# Driver_Morpheus_PONTE_H.net
KiCad netlist of a schematic drawn in Altium Designer
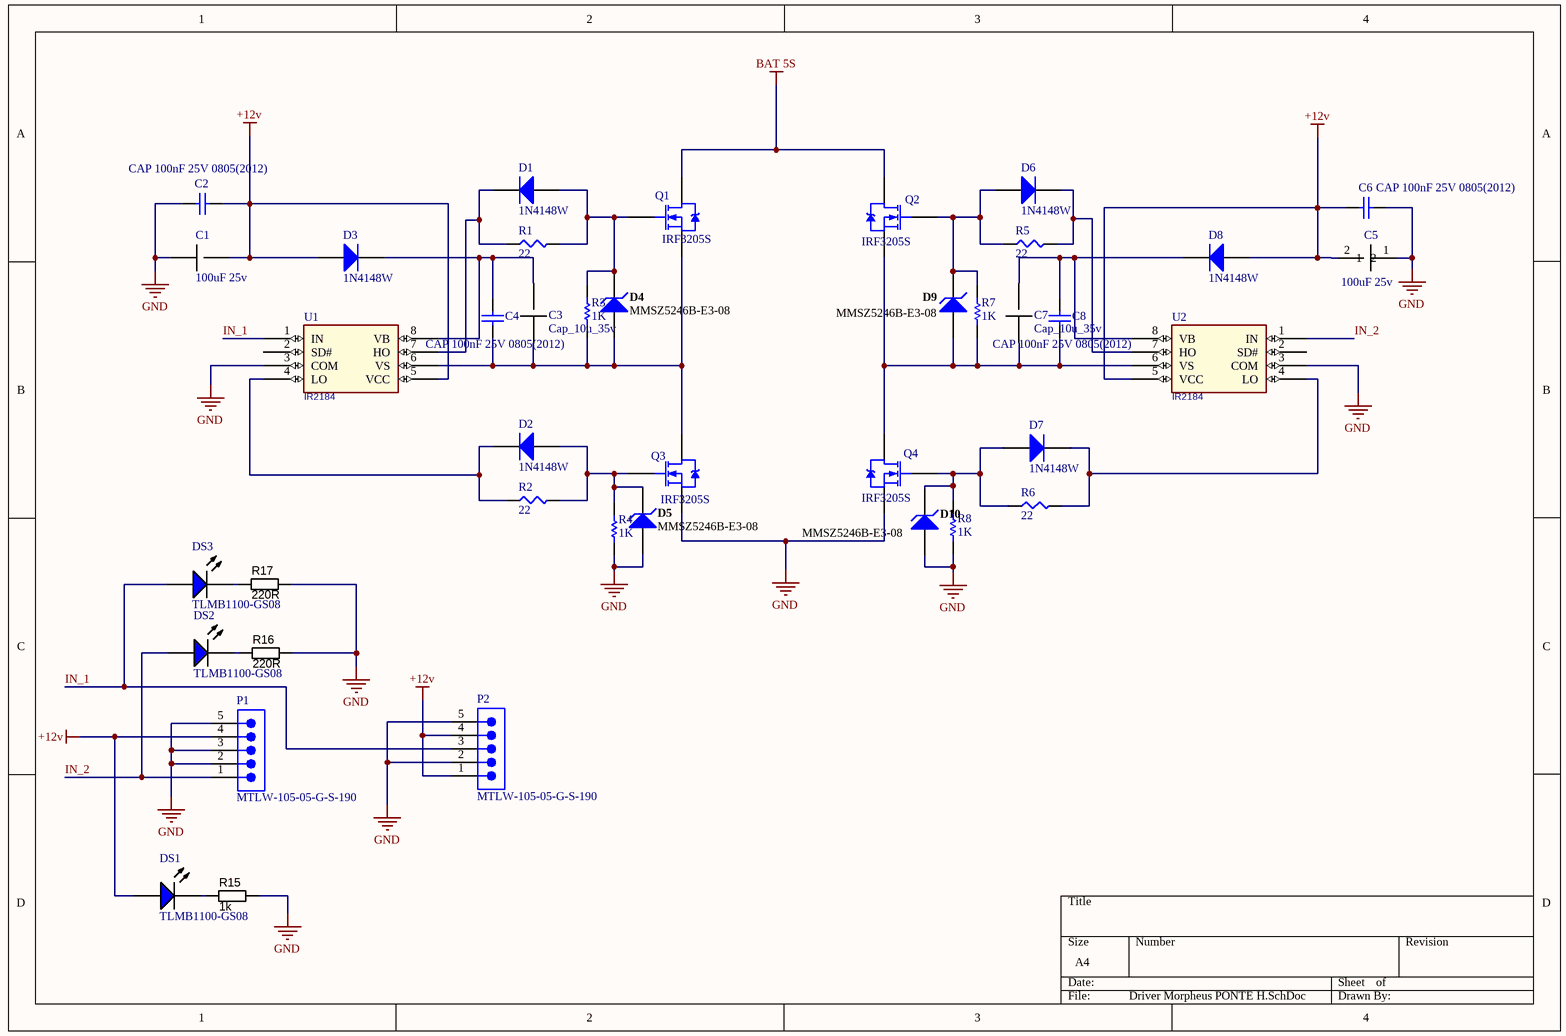
[diagram p0: Driver Morpheus PONTE H.SchDoc]

(export (version "E")
  (design (tool "Eeschema 10.0.6"))
  (components
    (comp (ref "C1")
      (value "100uF 25v")
      (footprint "CAPAE9083X70M")
      (libsource (lib "LibSanhaço2017") (part "Cap_10u_35v"))
    )
    (comp (ref "C2")
      (value "CAP 100nF 25V 0805(2012)")
      (footprint "CAPC0805(2012)145_M")
      (description "CAP 100nF 25V ±5% 0805 (2012 Metric) Thickness 1.45mm SMD")
      (fields (field (name "TOLERANCE") "Â±5%"))
      (libsource (lib "Altium Content Vault") (part "CAP"))
    )
    (comp (ref "C3")
      (value "Cap_10u_35v")
      (footprint "CAP POL 2917/7343")
      (libsource (lib "LibSanhaço2017") (part "Cap_10u_35v"))
    )
    (comp (ref "C4")
      (value "CAP 100nF 25V 0805(2012)")
      (footprint "CAPC0805(2012)145_M")
      (description "CAP 100nF 25V ±5% 0805 (2012 Metric) Thickness 1.45mm SMD")
      (fields (field (name "TOLERANCE") "Â±5%"))
      (libsource (lib "Altium Content Vault") (part "CAP"))
    )
    (comp (ref "C5")
      (value "100uF 25v")
      (footprint "CAPAE9083X70M")
      (description "Cap Tântalo")
      (libsource (lib "LibSanhaço2017") (part "Cap_100u_25v"))
    )
    (comp (ref "C6")
      (value "CAP 100nF 25V 0805(2012)")
      (footprint "CAPC0805(2012)145_M")
      (description "CAP 100nF 25V ±5% 0805 (2012 Metric) Thickness 1.45mm SMD")
      (fields (field (name "TOLERANCE") "Â±5%"))
      (libsource (lib "Altium Content Vault") (part "CAP"))
    )
    (comp (ref "C7")
      (value "Cap_10u_35v")
      (footprint "CAP POL 2917/7343")
      (libsource (lib "LibSanhaço2017") (part "Cap_10u_35v"))
    )
    (comp (ref "C8")
      (value "CAP 100nF 25V 0805(2012)")
      (footprint "CAPC0805(2012)145_M")
      (description "CAP 100nF 25V ±5% 0805 (2012 Metric) Thickness 1.45mm SMD")
      (fields (field (name "TOLERANCE") "Â±5%"))
      (libsource (lib "Altium Content Vault") (part "CAP"))
    )
    (comp (ref "D1")
      (value "1N4148W")
      (footprint "JSCJ-SOD-123-2_V")
      (description "Fast Switching Diode, 75 V, 150 mA, 2-Pin 2.7 x 1.6 x 1.25 mm SMD, Tape and Reel")
      (fields (field (name "MANUFACTURER") "Changjiang Electronics"))
      (libsource (lib "Altium Content Vault") (part "CMP-0914-00001-1"))
    )
    (comp (ref "D2")
      (value "1N4148W")
      (footprint "JSCJ-SOD-123-2_V")
      (description "Fast Switching Diode, 75 V, 150 mA, 2-Pin 2.7 x 1.6 x 1.25 mm SMD, Tape and Reel")
      (fields (field (name "MANUFACTURER") "Changjiang Electronics"))
      (libsource (lib "Altium Content Vault") (part "CMP-0914-00001-1"))
    )
    (comp (ref "D3")
      (value "1N4148W")
      (footprint "JSCJ-SOD-123-2_V")
      (description "Fast Switching Diode, 75 V, 150 mA, 2-Pin 2.7 x 1.6 x 1.25 mm SMD, Tape and Reel")
      (fields (field (name "MANUFACTURER") "Changjiang Electronics"))
      (libsource (lib "Altium Content Vault") (part "CMP-0914-00001-1"))
    )
    (comp (ref "D4")
      (value "MMSZ5246B-E3-08")
      (footprint "VISH-SOD-123-2_V")
      (description "Small Signal Zener Diode, 16 V +/- 5%, -55 to 155 degC, 2-Pin SOD-123, RoHS, Tape and Reel")
      (fields (field (name "MANUFACTURER") "Vishay Semiconductor") (field (name "TOLERANCE") "+/- 5%"))
      (libsource (lib "Altium Content Vault") (part "VISH-DZEN_A1K2-2"))
    )
    (comp (ref "D5")
      (value "MMSZ5246B-E3-08")
      (footprint "VISH-SOD-123-2_V")
      (description "Small Signal Zener Diode, 16 V +/- 5%, -55 to 155 degC, 2-Pin SOD-123, RoHS, Tape and Reel")
      (fields (field (name "MANUFACTURER") "Vishay Semiconductor") (field (name "TOLERANCE") "+/- 5%"))
      (libsource (lib "Altium Content Vault") (part "VISH-DZEN_A1K2-2"))
    )
    (comp (ref "D6")
      (value "1N4148W")
      (footprint "JSCJ-SOD-123-2_V")
      (description "Fast Switching Diode, 75 V, 150 mA, 2-Pin 2.7 x 1.6 x 1.25 mm SMD, Tape and Reel")
      (fields (field (name "MANUFACTURER") "Changjiang Electronics"))
      (libsource (lib "Altium Content Vault") (part "CMP-0914-00001-1"))
    )
    (comp (ref "D7")
      (value "1N4148W")
      (footprint "JSCJ-SOD-123-2_V")
      (description "Fast Switching Diode, 75 V, 150 mA, 2-Pin 2.7 x 1.6 x 1.25 mm SMD, Tape and Reel")
      (fields (field (name "MANUFACTURER") "Changjiang Electronics"))
      (libsource (lib "Altium Content Vault") (part "CMP-0914-00001-1"))
    )
    (comp (ref "D8")
      (value "1N4148W")
      (footprint "JSCJ-SOD-123-2_V")
      (description "Fast Switching Diode, 75 V, 150 mA, 2-Pin 2.7 x 1.6 x 1.25 mm SMD, Tape and Reel")
      (fields (field (name "MANUFACTURER") "Changjiang Electronics"))
      (libsource (lib "Altium Content Vault") (part "CMP-0914-00001-1"))
    )
    (comp (ref "D9")
      (value "MMSZ5246B-E3-08")
      (footprint "VISH-SOD-123-2_V")
      (description "Small Signal Zener Diode, 16 V +/- 5%, -55 to 155 degC, 2-Pin SOD-123, RoHS, Tape and Reel")
      (fields (field (name "MANUFACTURER") "Vishay Semiconductor") (field (name "TOLERANCE") "+/- 5%"))
      (libsource (lib "Altium Content Vault") (part "CMP-0931-00032-1"))
    )
    (comp (ref "D10")
      (value "MMSZ5246B-E3-08")
      (footprint "VISH-SOD-123-2_V")
      (description "Small Signal Zener Diode, 16 V +/- 5%, -55 to 155 degC, 2-Pin SOD-123, RoHS, Tape and Reel")
      (fields (field (name "MANUFACTURER") "Vishay Semiconductor") (field (name "TOLERANCE") "+/- 5%"))
      (libsource (lib "Altium Content Vault") (part "VISH-DZEN_A1K2-2"))
    )
    (comp (ref "DS1")
      (value "TLMB1100-GS08")
      (footprint "VISH-TLMX1100-2_V")
      (description "Blue LED, 10 mA, 3.9 V, -40 to 100 degC, 2-Pin SMD (0603), RoHS, Tape and Reel")
      (fields (field (name "TOLERANCE") "10%"))
      (libsource (lib "Altium Content Vault") (part "CMP-1666-00028-1"))
    )
    (comp (ref "DS2")
      (value "TLMB1100-GS08")
      (footprint "VISH-TLMX1100-2_V")
      (description "Blue LED, 10 mA, 3.9 V, -40 to 100 degC, 2-Pin SMD (0603), RoHS, Tape and Reel")
      (fields (field (name "TOLERANCE") "10%"))
      (libsource (lib "Altium Content Vault") (part "CMP-1666-00028-1"))
    )
    (comp (ref "DS3")
      (value "TLMB1100-GS08")
      (footprint "VISH-TLMX1100-2_V")
      (description "Blue LED, 10 mA, 3.9 V, -40 to 100 degC, 2-Pin SMD (0603), RoHS, Tape and Reel")
      (fields (field (name "TOLERANCE") "10%"))
      (libsource (lib "Altium Content Vault") (part "CMP-1666-00028-1"))
    )
    (comp (ref "P1")
      (value "MTLW-105-05-G-S-190")
      (footprint "SMTC-MTLW-105-05-X-S-190")
      (fields (field (name "MANUFACTURER") "Samtec"))
      (libsource (lib "Altium Content Vault") (part "SMTC-MTLW-105-05-X-S-190"))
    )
    (comp (ref "P2")
      (value "MTLW-105-05-G-S-190")
      (footprint "SMTC-MTLW-105-05-X-S-190")
      (fields (field (name "MANUFACTURER") "Samtec"))
      (libsource (lib "Altium Content Vault") (part "SMTC-MTLW-105-05-X-S-190"))
    )
    (comp (ref "Q1")
      (value "IRF3205S")
      (footprint "D2PAK_N")
      (description "HEXFET Power MOSFET")
      (fields (field (name "PUBLISHER") "Altium Limited"))
      (libsource (lib "IR Discrete MOSFET - Power") (part "IRF3205S"))
    )
    (comp (ref "Q2")
      (value "IRF3205S")
      (footprint "D2PAK_N")
      (description "HEXFET Power MOSFET")
      (fields (field (name "PUBLISHER") "Altium Limited"))
      (libsource (lib "IR Discrete MOSFET - Power") (part "IRF3205S"))
    )
    (comp (ref "Q3")
      (value "IRF3205S")
      (footprint "D2PAK_N")
      (description "HEXFET Power MOSFET")
      (fields (field (name "PUBLISHER") "Altium Limited"))
      (libsource (lib "IR Discrete MOSFET - Power") (part "IRF3205S"))
    )
    (comp (ref "Q4")
      (value "IRF3205S")
      (footprint "D2PAK_N")
      (description "HEXFET Power MOSFET")
      (fields (field (name "PUBLISHER") "Altium Limited"))
      (libsource (lib "IR Discrete MOSFET - Power") (part "IRF3205S"))
    )
    (comp (ref "R1")
      (value "22")
      (footprint "SMD-0603-RES")
      (description "RES SMD 22 OHM 1% 1/10W 0603")
      (fields
        (field (name "PART NUMBER") "ERJ-3EKF22R0V")
        (field (name "DIGI-KEY PART NUMBER") "P22.0HCT-ND")
      )
      (libsource (lib "Panasonic_ERJ_0603") (part "ERJ-3EKF22R0V"))
    )
    (comp (ref "R2")
      (value "22")
      (footprint "SMD-0603-RES")
      (description "RES SMD 22 OHM 1% 1/10W 0603")
      (fields
        (field (name "PART NUMBER") "ERJ-3EKF22R0V")
        (field (name "DIGI-KEY PART NUMBER") "P22.0HCT-ND")
      )
      (libsource (lib "Panasonic_ERJ_0603") (part "ERJ-3EKF22R0V"))
    )
    (comp (ref "R3")
      (value "1K")
      (footprint "RES-0402")
      (description "RES SMD 1K OHM 5% 1/16W 0402")
      (fields (field (name "Comment") "RC0402JR-071KL"))
      (libsource (lib "Schlib1") (part "RES 1K 0402"))
    )
    (comp (ref "R4")
      (value "1K")
      (footprint "RES-0402")
      (description "RES SMD 1K OHM 5% 1/16W 0402")
      (fields (field (name "Comment") "RC0402JR-071KL"))
      (libsource (lib "Schlib1") (part "RES 1K 0402"))
    )
    (comp (ref "R5")
      (value "22")
      (footprint "SMD-0603-RES")
      (description "RES SMD 22 OHM 1% 1/10W 0603")
      (fields
        (field (name "PART NUMBER") "ERJ-3EKF22R0V")
        (field (name "DIGI-KEY PART NUMBER") "P22.0HCT-ND")
      )
      (libsource (lib "Panasonic_ERJ_0603") (part "ERJ-3EKF22R0V"))
    )
    (comp (ref "R6")
      (value "22")
      (footprint "SMD-0603-RES")
      (description "RES SMD 22 OHM 1% 1/10W 0603")
      (fields
        (field (name "PART NUMBER") "ERJ-3EKF22R0V")
        (field (name "DIGI-KEY PART NUMBER") "P22.0HCT-ND")
      )
      (libsource (lib "Panasonic_ERJ_0603") (part "ERJ-3EKF22R0V"))
    )
    (comp (ref "R7")
      (value "1K")
      (footprint "RES-0402")
      (description "RES SMD 1K OHM 5% 1/16W 0402")
      (fields (field (name "Comment") "RC0402JR-071KL"))
      (libsource (lib "Schlib1") (part "RES 1K 0402"))
    )
    (comp (ref "R8")
      (value "1K")
      (footprint "RES-0402")
      (description "RES SMD 1K OHM 5% 1/16W 0402")
      (fields (field (name "Comment") "RC0402JR-071KL"))
      (libsource (lib "Schlib1") (part "RES 1K 0402"))
    )
    (comp (ref "R15")
      (value "1k")
      (footprint "RESC1608X55N")
      (description "Resistor SMD chip 220 Ohm 0.1W 5% 0603")
      (fields (field (name "TOLERANCE") "±5%") (field (name "Comment") "Thick Film"))
      (libsource (lib "PBL - Resistors") (part "RES_220R_0603_5%"))
    )
    (comp (ref "R16")
      (value "220R")
      (footprint "RESC1608X55N")
      (description "Resistor SMD chip 220 Ohm 0.1W 5% 0603")
      (fields (field (name "TOLERANCE") "±5%") (field (name "Comment") "Thick Film"))
      (libsource (lib "PBL - Resistors") (part "RES_220R_0603_5%"))
    )
    (comp (ref "R17")
      (value "220R")
      (footprint "RESC1608X55N")
      (description "Resistor SMD chip 220 Ohm 0.1W 5% 0603")
      (fields (field (name "TOLERANCE") "±5%") (field (name "Comment") "Thick Film"))
      (libsource (lib "PBL - Resistors") (part "RES_220R_0603_5%"))
    )
    (comp (ref "U1") (value "IR2184") (libsource (lib "") (part "IR2184_1")))
    (comp (ref "U2") (value "IR2184") (libsource (lib "IR2184_Library") (part "IR2184")))
  )
  (nets
    (net (code "1") (name "+12v") (class "Default")
      (node (ref "C1") (pin "2") (pinfunction "2_2") (pintype "passive"))
      (node (ref "C2") (pin "2") (pinfunction "2_2") (pintype "passive"))
      (node (ref "C5") (pin "2") (pinfunction "2_2") (pintype "passive"))
      (node (ref "C6") (pin "2") (pinfunction "2_2") (pintype "passive"))
      (node (ref "D3") (pin "1") (pinfunction "+_1") (pintype "passive"))
      (node (ref "D8") (pin "1") (pinfunction "+_1") (pintype "passive"))
      (node (ref "DS1") (pin "1") (pinfunction "A_1") (pintype "passive"))
      (node (ref "P1") (pin "4") (pinfunction "4_4") (pintype "passive"))
      (node (ref "P2") (pin "1") (pinfunction "1_1") (pintype "passive"))
      (node (ref "P2") (pin "4") (pinfunction "4_4") (pintype "passive"))
      (node (ref "U1") (pin "5") (pinfunction "VCC_5") (pintype "bidirectional"))
      (node (ref "U2") (pin "5") (pinfunction "VCC_5") (pintype "bidirectional"))
    )
    (net (code "2") (name "/IN_1") (class "Default")
      (node (ref "DS3") (pin "1") (pinfunction "A_1") (pintype "passive"))
      (node (ref "P2") (pin "3") (pinfunction "3_3") (pintype "passive"))
      (node (ref "U1") (pin "1") (pinfunction "IN_1") (pintype "bidirectional"))
    )
    (net (code "3") (name "/IN_2") (class "Default")
      (node (ref "DS2") (pin "1") (pinfunction "A_1") (pintype "passive"))
      (node (ref "P1") (pin "1") (pinfunction "1_1") (pintype "passive"))
      (node (ref "U2") (pin "1") (pinfunction "IN_1") (pintype "bidirectional"))
    )
    (net (code "4") (name "BAT 5S") (class "Default")
      (node (ref "Q1") (pin "2") (pinfunction "D_2") (pintype "passive"))
      (node (ref "Q2") (pin "2") (pinfunction "D_2") (pintype "passive"))
    )
    (net (code "5") (name "GND") (class "Default")
      (node (ref "C1") (pin "1") (pinfunction "1_1") (pintype "passive"))
      (node (ref "C2") (pin "1") (pinfunction "1_1") (pintype "passive"))
      (node (ref "C5") (pin "1") (pinfunction "1_1") (pintype "passive"))
      (node (ref "C6") (pin "1") (pinfunction "1_1") (pintype "passive"))
      (node (ref "D10") (pin "1") (pinfunction "A_1") (pintype "passive"))
      (node (ref "D5") (pin "1") (pinfunction "A_1") (pintype "passive"))
      (node (ref "P1") (pin "2") (pinfunction "2_2") (pintype "passive"))
      (node (ref "P1") (pin "3") (pinfunction "3_3") (pintype "passive"))
      (node (ref "P1") (pin "5") (pinfunction "5_5") (pintype "passive"))
      (node (ref "P2") (pin "2") (pinfunction "2_2") (pintype "passive"))
      (node (ref "P2") (pin "5") (pinfunction "5_5") (pintype "passive"))
      (node (ref "Q3") (pin "3") (pinfunction "S_3") (pintype "passive"))
      (node (ref "Q4") (pin "3") (pinfunction "S_3") (pintype "passive"))
      (node (ref "R15") (pin "2") (pinfunction "2_2") (pintype "passive"))
      (node (ref "R16") (pin "2") (pinfunction "2_2") (pintype "passive"))
      (node (ref "R17") (pin "2") (pinfunction "2_2") (pintype "passive"))
      (node (ref "R4") (pin "1") (pinfunction "1_1") (pintype "passive"))
      (node (ref "R8") (pin "1") (pinfunction "1_1") (pintype "passive"))
      (node (ref "U1") (pin "3") (pinfunction "COM_3") (pintype "bidirectional"))
      (node (ref "U2") (pin "3") (pinfunction "COM_3") (pintype "bidirectional"))
    )
    (net (code "6") (name "Net-(D1-+)") (class "Default")
      (node (ref "D1") (pin "1") (pinfunction "+_1") (pintype "passive"))
      (node (ref "D4") (pin "2") (pinfunction "K_2") (pintype "passive"))
      (node (ref "Q1") (pin "1") (pinfunction "G_1") (pintype "passive"))
      (node (ref "R1") (pin "2") (pinfunction "2_2") (pintype "passive"))
      (node (ref "R3") (pin "2") (pinfunction "2_2") (pintype "passive"))
    )
    (net (code "7") (name "Net-(D1--)") (class "Default")
      (node (ref "D1") (pin "2") (pinfunction "-_2") (pintype "passive"))
      (node (ref "R1") (pin "1") (pinfunction "1_1") (pintype "passive"))
      (node (ref "U1") (pin "7") (pinfunction "HO_7") (pintype "bidirectional"))
    )
    (net (code "8") (name "Net-(D2-+)") (class "Default")
      (node (ref "D2") (pin "1") (pinfunction "+_1") (pintype "passive"))
      (node (ref "D5") (pin "2") (pinfunction "K_2") (pintype "passive"))
      (node (ref "Q3") (pin "1") (pinfunction "G_1") (pintype "passive"))
      (node (ref "R2") (pin "2") (pinfunction "2_2") (pintype "passive"))
      (node (ref "R4") (pin "2") (pinfunction "2_2") (pintype "passive"))
    )
    (net (code "9") (name "Net-(D2--)") (class "Default")
      (node (ref "D2") (pin "2") (pinfunction "-_2") (pintype "passive"))
      (node (ref "R2") (pin "1") (pinfunction "1_1") (pintype "passive"))
      (node (ref "U1") (pin "4") (pinfunction "LO_4") (pintype "bidirectional"))
    )
    (net (code "10") (name "Net-(D3--)") (class "Default")
      (node (ref "C3") (pin "2") (pinfunction "2_2") (pintype "passive"))
      (node (ref "C4") (pin "2") (pinfunction "2_2") (pintype "passive"))
      (node (ref "D3") (pin "2") (pinfunction "-_2") (pintype "passive"))
      (node (ref "U1") (pin "8") (pinfunction "VB_8") (pintype "bidirectional"))
    )
    (net (code "11") (name "Net-(D4-A)") (class "Default")
      (node (ref "C3") (pin "1") (pinfunction "1_1") (pintype "passive"))
      (node (ref "C4") (pin "1") (pinfunction "1_1") (pintype "passive"))
      (node (ref "D4") (pin "1") (pinfunction "A_1") (pintype "passive"))
      (node (ref "Q1") (pin "3") (pinfunction "S_3") (pintype "passive"))
      (node (ref "Q3") (pin "2") (pinfunction "D_2") (pintype "passive"))
      (node (ref "R3") (pin "1") (pinfunction "1_1") (pintype "passive"))
      (node (ref "U1") (pin "6") (pinfunction "VS_6") (pintype "bidirectional"))
    )
    (net (code "12") (name "Net-(D6-+)") (class "Default")
      (node (ref "D6") (pin "1") (pinfunction "+_1") (pintype "passive"))
      (node (ref "D9") (pin "2") (pinfunction "K_2") (pintype "passive"))
      (node (ref "Q2") (pin "1") (pinfunction "G_1") (pintype "passive"))
      (node (ref "R5") (pin "1") (pinfunction "1_1") (pintype "passive"))
      (node (ref "R7") (pin "2") (pinfunction "2_2") (pintype "passive"))
    )
    (net (code "13") (name "Net-(D6--)") (class "Default")
      (node (ref "D6") (pin "2") (pinfunction "-_2") (pintype "passive"))
      (node (ref "R5") (pin "2") (pinfunction "2_2") (pintype "passive"))
      (node (ref "U2") (pin "7") (pinfunction "HO_7") (pintype "bidirectional"))
    )
    (net (code "14") (name "Net-(D7--)") (class "Default")
      (node (ref "D7") (pin "2") (pinfunction "-_2") (pintype "passive"))
      (node (ref "R6") (pin "2") (pinfunction "2_2") (pintype "passive"))
      (node (ref "U2") (pin "4") (pinfunction "LO_4") (pintype "bidirectional"))
    )
    (net (code "15") (name "Net-(D8--)") (class "Default")
      (node (ref "C7") (pin "2") (pinfunction "2_2") (pintype "passive"))
      (node (ref "C8") (pin "2") (pinfunction "2_2") (pintype "passive"))
      (node (ref "D8") (pin "2") (pinfunction "-_2") (pintype "passive"))
      (node (ref "U2") (pin "8") (pinfunction "VB_8") (pintype "bidirectional"))
    )
    (net (code "16") (name "Net-(D9-A)") (class "Default")
      (node (ref "C7") (pin "1") (pinfunction "1_1") (pintype "passive"))
      (node (ref "C8") (pin "1") (pinfunction "1_1") (pintype "passive"))
      (node (ref "D9") (pin "1") (pinfunction "A_1") (pintype "passive"))
      (node (ref "Q2") (pin "3") (pinfunction "S_3") (pintype "passive"))
      (node (ref "Q4") (pin "2") (pinfunction "D_2") (pintype "passive"))
      (node (ref "R7") (pin "1") (pinfunction "1_1") (pintype "passive"))
      (node (ref "U2") (pin "6") (pinfunction "VS_6") (pintype "bidirectional"))
    )
    (net (code "17") (name "Net-(D10-K)") (class "Default")
      (node (ref "D10") (pin "2") (pinfunction "K_2") (pintype "passive"))
      (node (ref "D7") (pin "1") (pinfunction "+_1") (pintype "passive"))
      (node (ref "Q4") (pin "1") (pinfunction "G_1") (pintype "passive"))
      (node (ref "R6") (pin "1") (pinfunction "1_1") (pintype "passive"))
      (node (ref "R8") (pin "2") (pinfunction "2_2") (pintype "passive"))
    )
    (net (code "18") (name "Net-(DS1-K)") (class "Default")
      (node (ref "DS1") (pin "2") (pinfunction "K_2") (pintype "passive"))
      (node (ref "R15") (pin "1") (pinfunction "1_1") (pintype "passive"))
    )
    (net (code "19") (name "Net-(DS2-K)") (class "Default")
      (node (ref "DS2") (pin "2") (pinfunction "K_2") (pintype "passive"))
      (node (ref "R16") (pin "1") (pinfunction "1_1") (pintype "passive"))
    )
    (net (code "20") (name "Net-(DS3-K)") (class "Default")
      (node (ref "DS3") (pin "2") (pinfunction "K_2") (pintype "passive"))
      (node (ref "R17") (pin "1") (pinfunction "1_1") (pintype "passive"))
    )
    (net (code "21") (name "unconnected-(U1-SD#-Pad2)") (class "Default")
      (node (ref "U1") (pin "2") (pinfunction "SD#_2") (pintype "bidirectional"))
    )
    (net (code "22") (name "unconnected-(U2-SD#-Pad2)") (class "Default")
      (node (ref "U2") (pin "2") (pinfunction "SD#_2") (pintype "bidirectional"))
    )
  )
)
